# CONNECTOR_EXP.net
KiCad netlist of a schematic drawn in Altium Designer
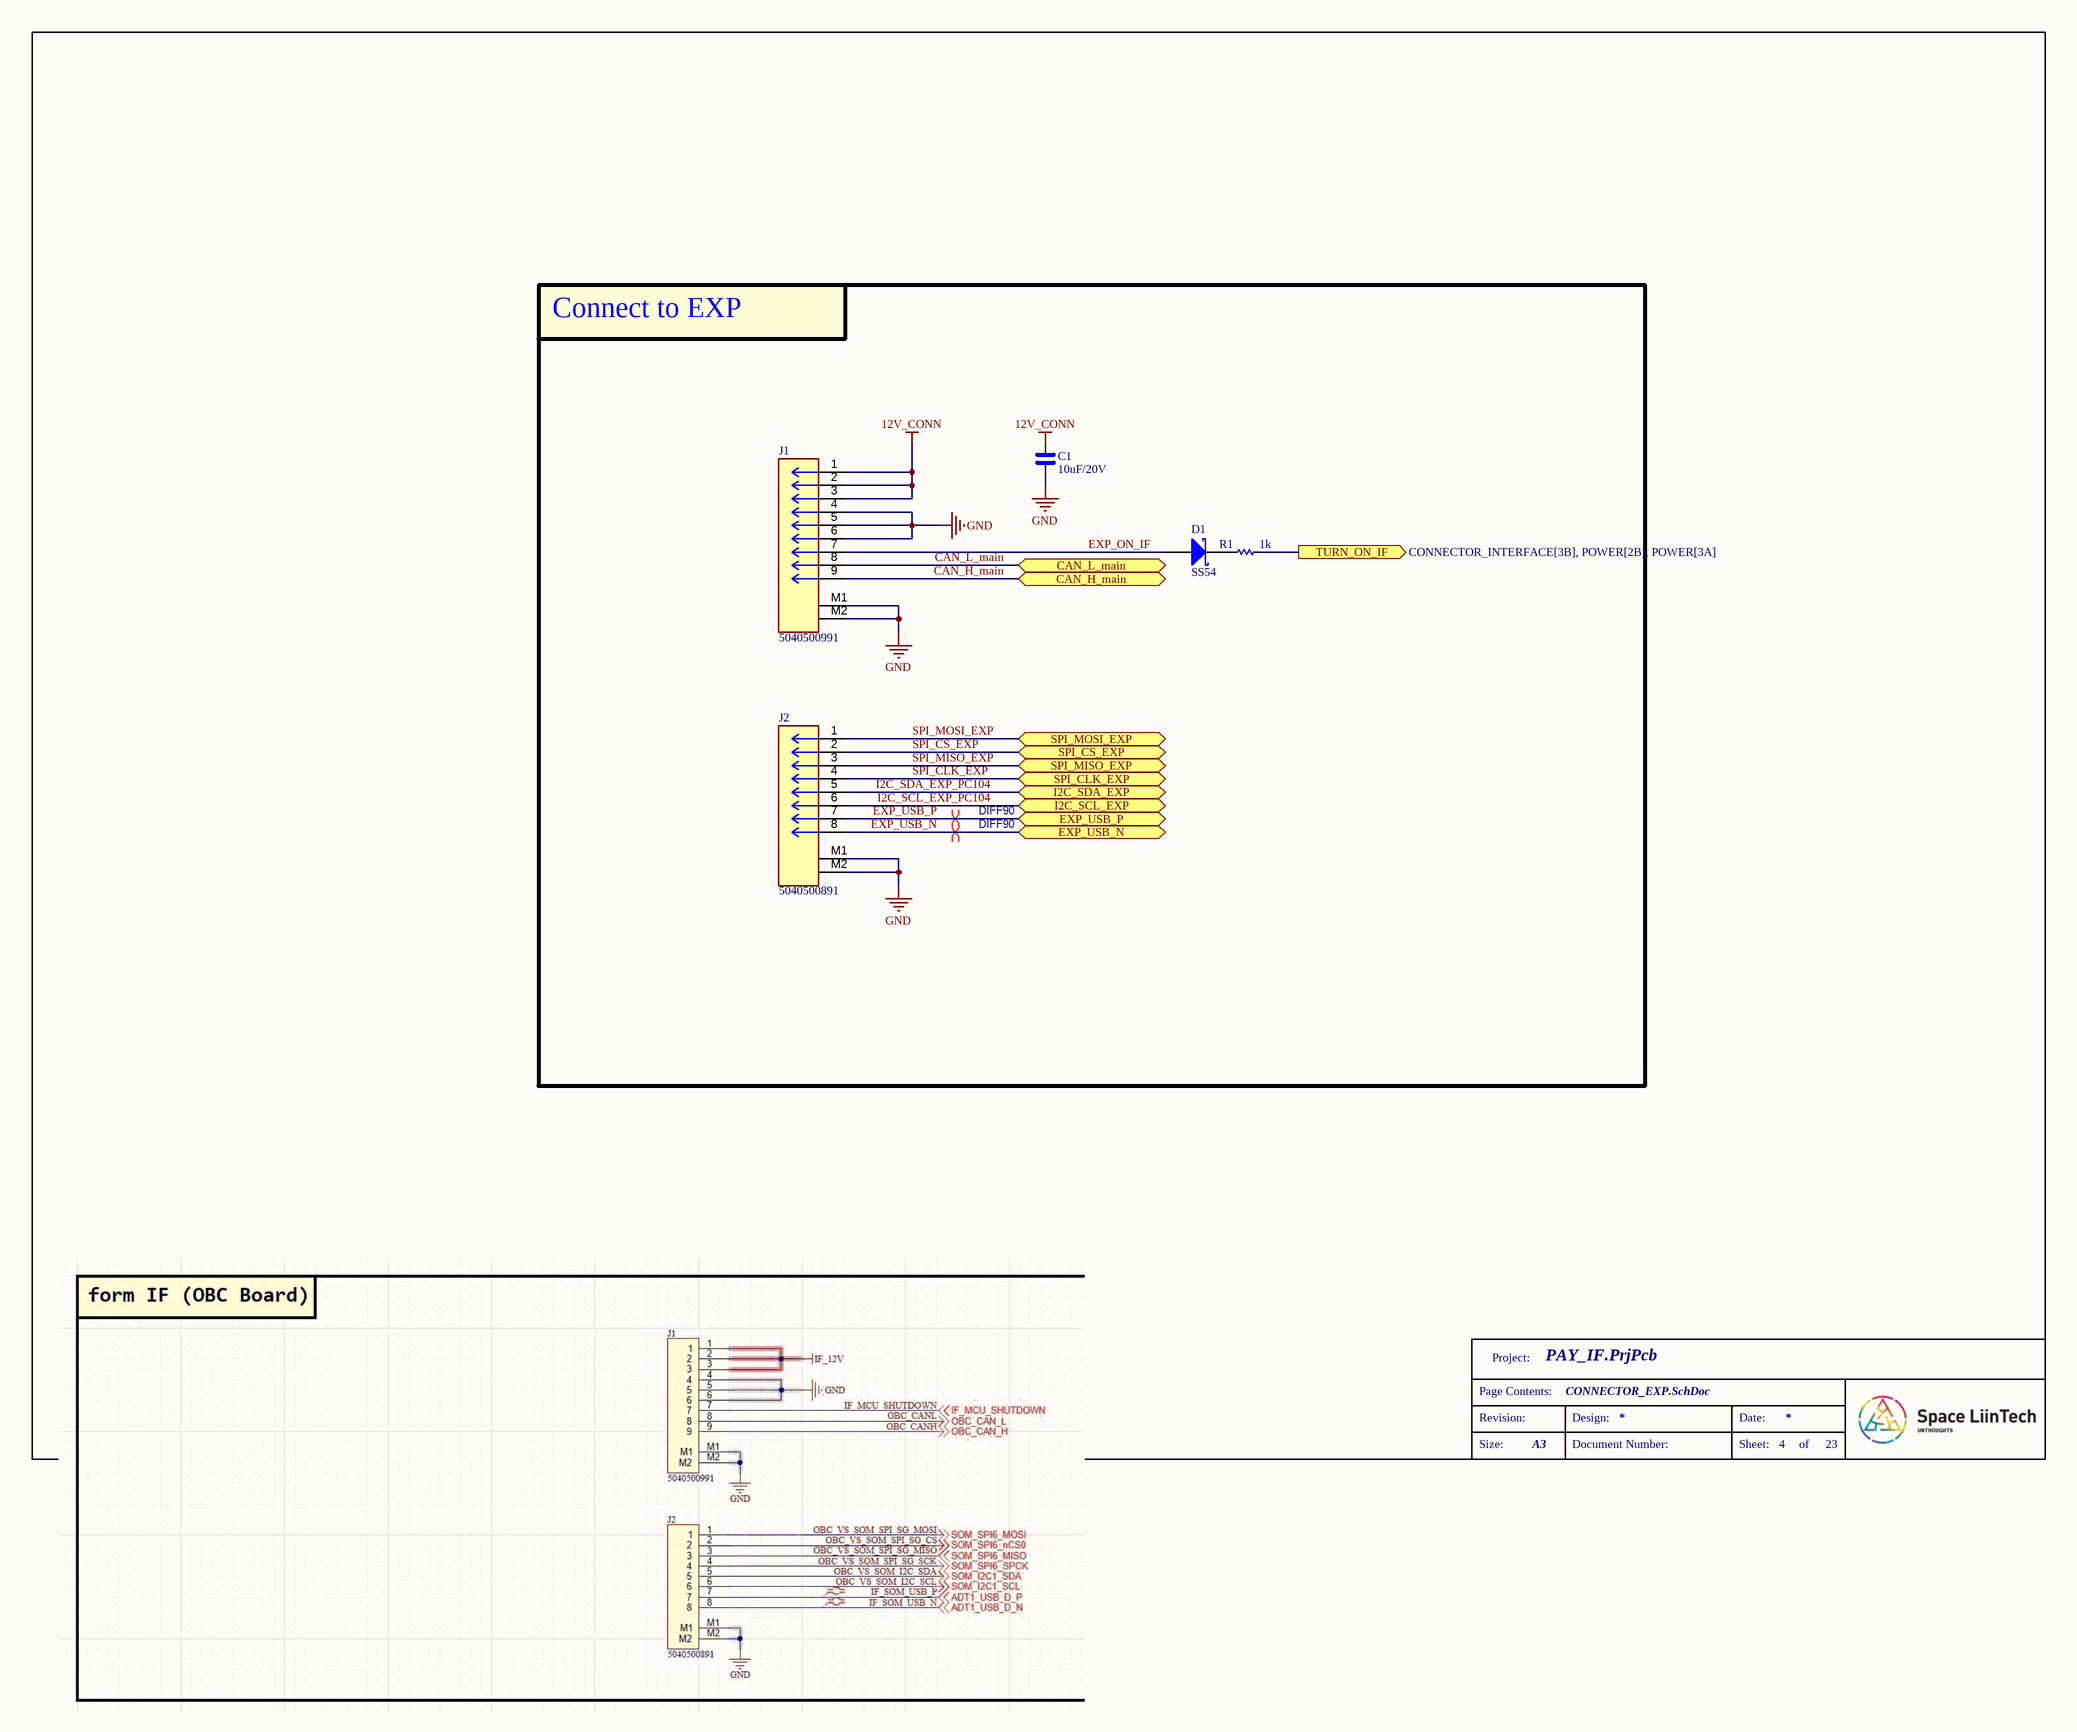
[diagram p0: CONNECTOR_EXP.SchDoc]

(export (version "E")
  (design (tool "Eeschema 10.0.6"))
  (components
    (comp (ref "C1")
      (value "10uF/20V")
      (footprint "CAP_C_2012X110")
      (description "CAP CHIP High Value")
      (libsource (lib "IFBschelib") (part "_CAP_C_High_2"))
    )
    (comp (ref "D1")
      (value "SS54")
      (footprint "DO-214AC_SMA")
      (description "DIODE SCHOTTKY 40V 5A SMA")
      (fields (field (name "MPN") "SS34"))
      (libsource (lib "IFBschelib") (part "SS54"))
    )
    (comp (ref "J1")
      (value "5040500991")
      (footprint "MOLEX_5040500991")
      (description "Connector Header Surface Mount, Right Angle 9 position 0.059\" (1.50mm)")
      (libsource (lib "IFBschelib") (part "5040500991"))
    )
    (comp (ref "J2")
      (value "5040500891")
      (footprint "MOLEX_5040500891")
      (description "Connector Header Surface Mount, Right Angle 8 position 0.059\" (1.50mm)`")
      (libsource (lib "IFBschelib") (part "5040500891"))
    )
    (comp (ref "R1")
      (value "1k")
      (footprint "RES_C_1005x30_L")
      (description "RES")
      (libsource (lib "IFBschelib") (part "_RES_B_2"))
    )
  )
  (nets
    (net (code "1") (name "/CAN_H_main") (class "Default")
      (node (ref "J1") (pin "9") (pinfunction "9_9") (pintype "passive"))
    )
    (net (code "2") (name "/CAN_L_main") (class "Default")
      (node (ref "J1") (pin "8") (pinfunction "8_8") (pintype "passive"))
    )
    (net (code "3") (name "/EXP_ON_IF") (class "Default")
      (node (ref "D1") (pin "1") (pinfunction "A_1") (pintype "passive"))
      (node (ref "J1") (pin "7") (pinfunction "7_7") (pintype "passive"))
    )
    (net (code "4") (name "/EXP_USB_N") (class "Default")
      (node (ref "J2") (pin "8") (pinfunction "8_8") (pintype "passive"))
    )
    (net (code "5") (name "/EXP_USB_P") (class "Default")
      (node (ref "J2") (pin "7") (pinfunction "7_7") (pintype "passive"))
    )
    (net (code "6") (name "/I2C_SCL_EXP_PC104") (class "Default")
      (node (ref "J2") (pin "6") (pinfunction "6_6") (pintype "passive"))
    )
    (net (code "7") (name "/I2C_SDA_EXP_PC104") (class "Default")
      (node (ref "J2") (pin "5") (pinfunction "5_5") (pintype "passive"))
    )
    (net (code "8") (name "/SPI_CLK_EXP") (class "Default")
      (node (ref "J2") (pin "4") (pinfunction "4_4") (pintype "passive"))
    )
    (net (code "9") (name "/SPI_CS_EXP") (class "Default")
      (node (ref "J2") (pin "2") (pinfunction "2_2") (pintype "passive"))
    )
    (net (code "10") (name "/SPI_MISO_EXP") (class "Default")
      (node (ref "J2") (pin "3") (pinfunction "3_3") (pintype "passive"))
    )
    (net (code "11") (name "/SPI_MOSI_EXP") (class "Default")
      (node (ref "J2") (pin "1") (pinfunction "1_1") (pintype "passive"))
    )
    (net (code "12") (name "/TURN_ON_IF") (class "Default")
      (node (ref "R1") (pin "2") (pinfunction "2_2") (pintype "passive"))
    )
    (net (code "13") (name "12V_CONN") (class "Default")
      (node (ref "C1") (pin "2") (pinfunction "2_2") (pintype "passive"))
      (node (ref "J1") (pin "1") (pinfunction "1_1") (pintype "passive"))
      (node (ref "J1") (pin "2") (pinfunction "2_2") (pintype "passive"))
      (node (ref "J1") (pin "3") (pinfunction "3_3") (pintype "passive"))
    )
    (net (code "14") (name "GND") (class "Default")
      (node (ref "C1") (pin "1") (pinfunction "1_1") (pintype "passive"))
      (node (ref "J1") (pin "4") (pinfunction "4_4") (pintype "passive"))
      (node (ref "J1") (pin "5") (pinfunction "5_5") (pintype "passive"))
      (node (ref "J1") (pin "6") (pinfunction "6_6") (pintype "passive"))
      (node (ref "J1") (pin "M1") (pinfunction "M1_M1") (pintype "passive"))
      (node (ref "J1") (pin "M2") (pinfunction "M2_M2") (pintype "passive"))
      (node (ref "J2") (pin "M1") (pinfunction "M1_M1") (pintype "passive"))
      (node (ref "J2") (pin "M2") (pinfunction "M2_M2") (pintype "passive"))
    )
    (net (code "15") (name "Net-(D1-K)") (class "Default")
      (node (ref "D1") (pin "2") (pinfunction "K_2") (pintype "passive"))
      (node (ref "R1") (pin "1") (pinfunction "1_1") (pintype "passive"))
    )
  )
)
